# CSS811_CO2_TVOC_Breakout-Mill.net
KiCad netlist of a schematic drawn in EAGLE
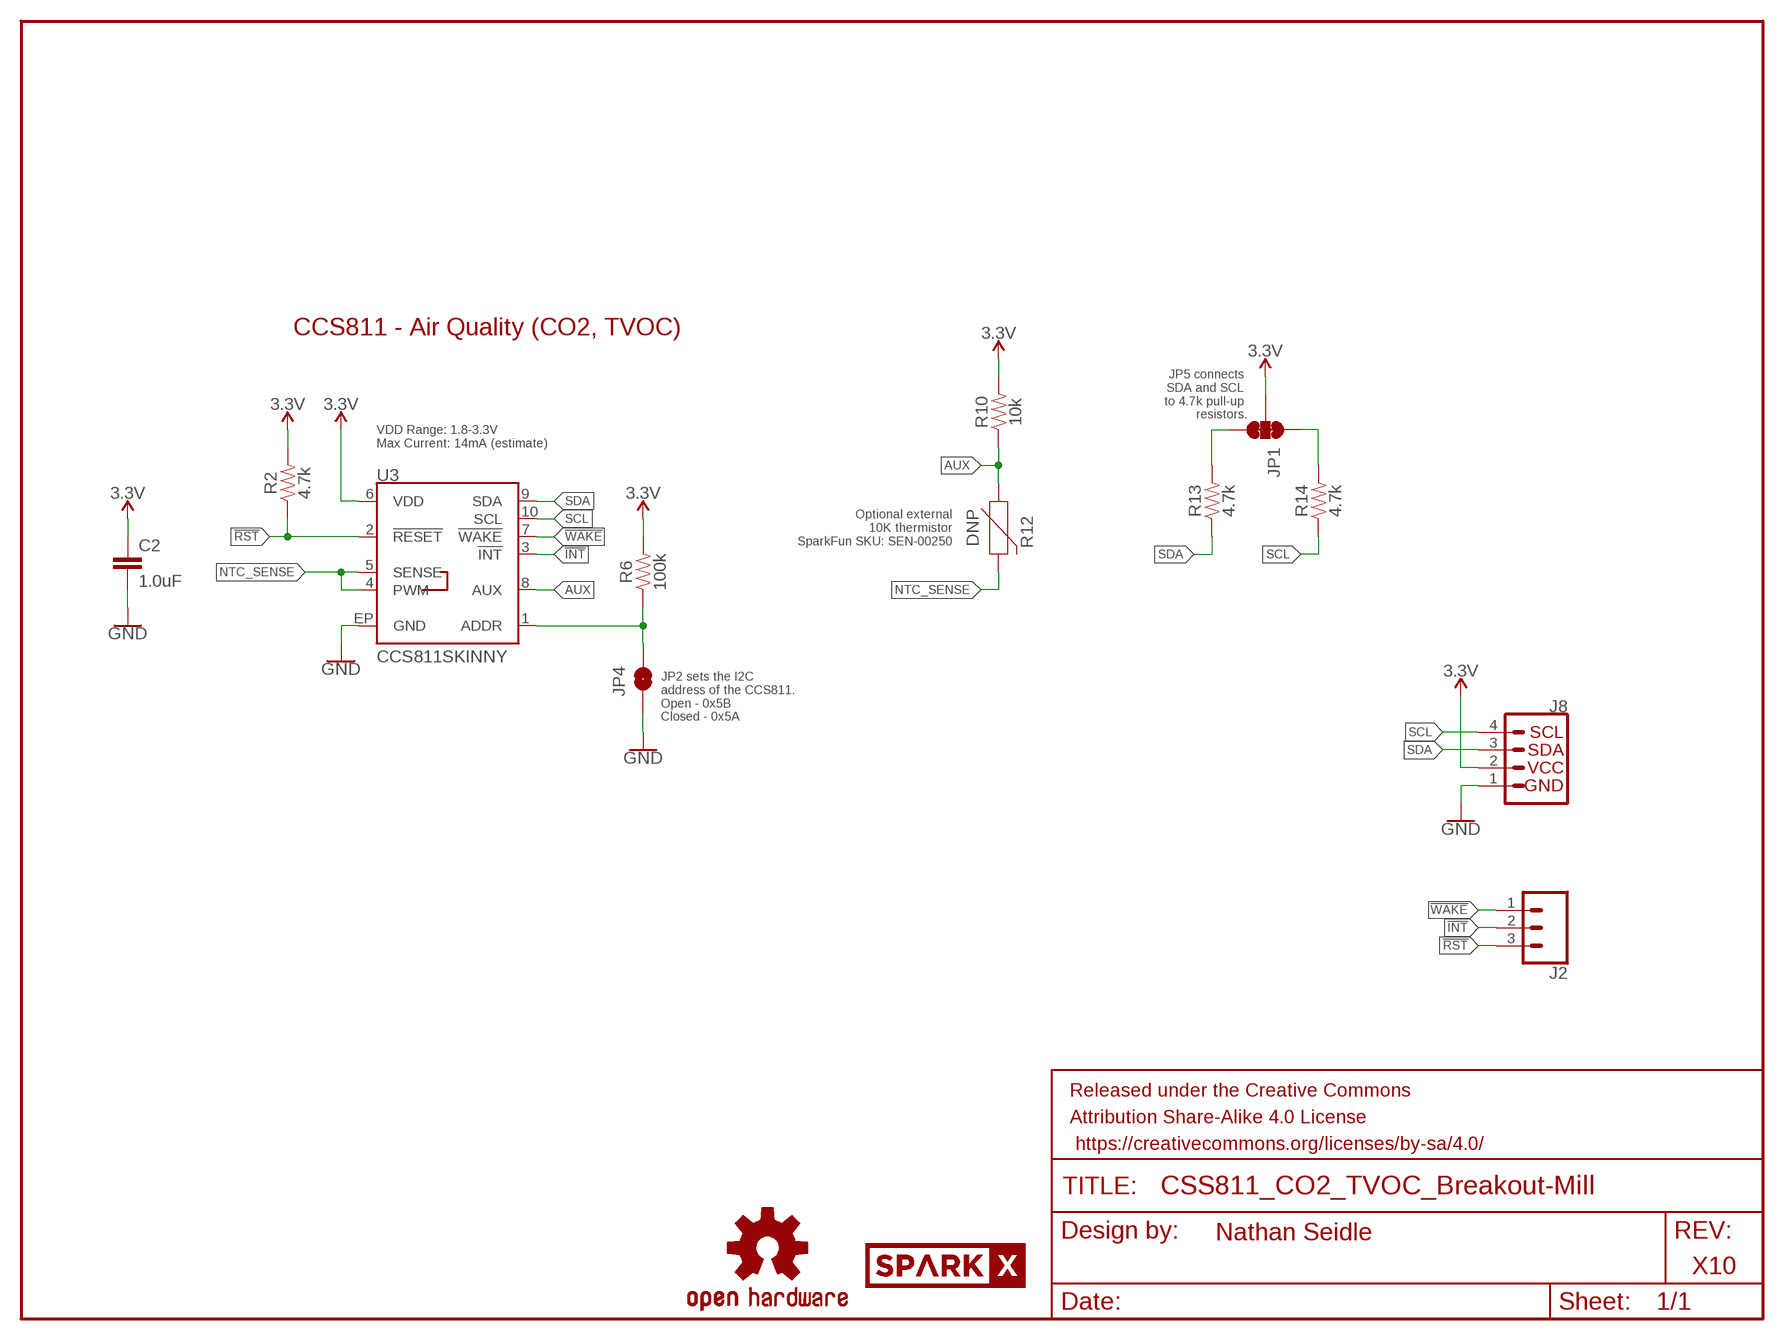
[diagram p0: schematic, sheet 1]

(export (version "E")
  (design (tool "Eeschema 10.0.6"))
  (components
    (comp (ref "C2")
      (value "1.0uF")
      (footprint "eagle-import:0603")
      (libsource (lib "eagle-import") (part "1.0UF-0603-16V-10%"))
    )
    (comp (ref "FRAME1")
      (value "FRAME-LETTER")
      (footprint "eagle-import:CREATIVE_COMMONS")
      (libsource (lib "eagle-import") (part "FRAME-LETTER"))
    )
    (comp (ref "J2")
      (value "CONN_031X03_NO_SILK")
      (footprint "eagle-import:1X03_NO_SILK")
      (libsource (lib "eagle-import") (part "CONN_031X03_NO_SILK"))
    )
    (comp (ref "J8")
      (value "I2C_STANDARD_NO_SILK")
      (footprint "eagle-import:1X04_NO_SILK")
      (libsource (lib "eagle-import") (part "I2C_STANDARD_NO_SILK"))
    )
    (comp (ref "JP1")
      (value "JUMPER-SMT_3_2-NC_TRACE_SILK")
      (footprint "eagle-import:SMT-JUMPER_3_2-NC_TRACE_SILK")
      (libsource (lib "eagle-import") (part "JUMPER-SMT_3_2-NC_TRACE_SILK"))
    )
    (comp (ref "JP4")
      (value "JUMPER-SMT_2_NO_SILK")
      (footprint "eagle-import:SMT-JUMPER_2_NO_SILK")
      (libsource (lib "eagle-import") (part "JUMPER-SMT_2_NO_SILK"))
    )
    (comp (ref "LOGO4")
      (value "OSHW-LOGOS")
      (footprint "eagle-import:OSHW-LOGO-S")
      (libsource (lib "eagle-import") (part "OSHW-LOGOS"))
    )
    (comp (ref "R2")
      (value "4.7k")
      (footprint "eagle-import:0603")
      (libsource (lib "eagle-import") (part "4.7KOHM-0603-1/10W-1%"))
    )
    (comp (ref "R6")
      (value "100k")
      (footprint "eagle-import:0603")
      (libsource (lib "eagle-import") (part "100KOHM-0603-1/10W-1%"))
    )
    (comp (ref "R10")
      (value "10k")
      (footprint "eagle-import:0603")
      (libsource (lib "eagle-import") (part "10KOHM-0603-1/10W-1%"))
    )
    (comp (ref "R12")
      (value "DNP")
      (footprint "eagle-import:AXIAL-0.1")
      (fields (field (name "PROD_ID") "N/A"))
      (libsource (lib "eagle-import") (part "NTC-THERMISTOR-AXIAL-0.1"))
    )
    (comp (ref "R13")
      (value "4.7k")
      (footprint "eagle-import:0603")
      (libsource (lib "eagle-import") (part "4.7KOHM-0603-1/10W-1%"))
    )
    (comp (ref "R14")
      (value "4.7k")
      (footprint "eagle-import:0603")
      (libsource (lib "eagle-import") (part "4.7KOHM-0603-1/10W-1%"))
    )
    (comp (ref "U$1")
      (value "SPARKX-LOGO3")
      (footprint "eagle-import:SPARKX-SMALL")
      (libsource (lib "eagle-import") (part "SPARKX-LOGO3"))
    )
    (comp (ref "U3")
      (value "CCS811SKINNY")
      (footprint "eagle-import:LGA10-MILLABLE")
      (libsource (lib "eagle-import") (part "CCS811SKINNY"))
    )
  )
  (nets
    (net (code "1") (name "/~{INT}") (class "Default")
      (node (ref "J2") (pin "2") (pinfunction "2_2") (pintype "passive"))
      (node (ref "U3") (pin "3") (pinfunction "~{INT}_3") (pintype "bidirectional"))
    )
    (net (code "2") (name "/~{RST}") (class "Default")
      (node (ref "J2") (pin "3") (pinfunction "3_3") (pintype "passive"))
      (node (ref "R2") (pin "1") (pinfunction "1_1") (pintype "passive"))
      (node (ref "U3") (pin "2") (pinfunction "~{RESET}_2") (pintype "bidirectional"))
    )
    (net (code "3") (name "/~{WAKE}") (class "Default")
      (node (ref "J2") (pin "1") (pinfunction "1_1") (pintype "passive"))
      (node (ref "U3") (pin "7") (pinfunction "~{WAKE}_7") (pintype "bidirectional"))
    )
    (net (code "4") (name "3.3V") (class "Default")
      (node (ref "C2") (pin "1") (pinfunction "1_1") (pintype "passive"))
      (node (ref "J8") (pin "2") (pinfunction "2_2") (pintype "power_in"))
      (node (ref "JP1") (pin "2") (pinfunction "2_2") (pintype "passive"))
      (node (ref "R10") (pin "2") (pinfunction "2_2") (pintype "passive"))
      (node (ref "R2") (pin "2") (pinfunction "2_2") (pintype "passive"))
      (node (ref "R6") (pin "2") (pinfunction "2_2") (pintype "passive"))
      (node (ref "U3") (pin "6") (pinfunction "VDD_6") (pintype "bidirectional"))
    )
    (net (code "5") (name "AUX") (class "Default")
      (node (ref "R10") (pin "1") (pinfunction "1_1") (pintype "passive"))
      (node (ref "R12") (pin "P$1") (pinfunction "1_P$1") (pintype "bidirectional"))
      (node (ref "U3") (pin "8") (pinfunction "AUX_8") (pintype "bidirectional"))
    )
    (net (code "6") (name "GND") (class "Default")
      (node (ref "C2") (pin "2") (pinfunction "2_2") (pintype "passive"))
      (node (ref "J8") (pin "1") (pinfunction "1_1") (pintype "power_in"))
      (node (ref "JP4") (pin "1") (pinfunction "1_1") (pintype "passive"))
      (node (ref "U3") (pin "EP") (pinfunction "GND_EP") (pintype "bidirectional"))
    )
    (net (code "7") (name "NTC_SENSE") (class "Default")
      (node (ref "R12") (pin "P$2") (pinfunction "2_P$2") (pintype "bidirectional"))
      (node (ref "U3") (pin "4") (pinfunction "PWM_4") (pintype "bidirectional"))
      (node (ref "U3") (pin "5") (pinfunction "SENSE_5") (pintype "bidirectional"))
    )
    (net (code "8") (name "Net-(JP1-Pad1)") (class "Default")
      (node (ref "JP1") (pin "1") (pinfunction "1_1") (pintype "passive"))
      (node (ref "R14") (pin "2") (pinfunction "2_2") (pintype "passive"))
    )
    (net (code "9") (name "Net-(JP1-Pad3)") (class "Default")
      (node (ref "JP1") (pin "3") (pinfunction "3_3") (pintype "passive"))
      (node (ref "R13") (pin "2") (pinfunction "2_2") (pintype "passive"))
    )
    (net (code "10") (name "Net-(U3-ADDR)") (class "Default")
      (node (ref "JP4") (pin "2") (pinfunction "2_2") (pintype "passive"))
      (node (ref "R6") (pin "1") (pinfunction "1_1") (pintype "passive"))
      (node (ref "U3") (pin "1") (pinfunction "ADDR_1") (pintype "bidirectional"))
    )
    (net (code "11") (name "SCL") (class "Default")
      (node (ref "J8") (pin "4") (pinfunction "4_4") (pintype "passive"))
      (node (ref "R14") (pin "1") (pinfunction "1_1") (pintype "passive"))
      (node (ref "U3") (pin "10") (pinfunction "SCL_10") (pintype "bidirectional"))
    )
    (net (code "12") (name "SDA") (class "Default")
      (node (ref "J8") (pin "3") (pinfunction "3_3") (pintype "passive"))
      (node (ref "R13") (pin "1") (pinfunction "1_1") (pintype "passive"))
      (node (ref "U3") (pin "9") (pinfunction "SDA_9") (pintype "bidirectional"))
    )
  )
)
